# Irrigatron.net
KiCad netlist of a schematic drawn in EasyEDA
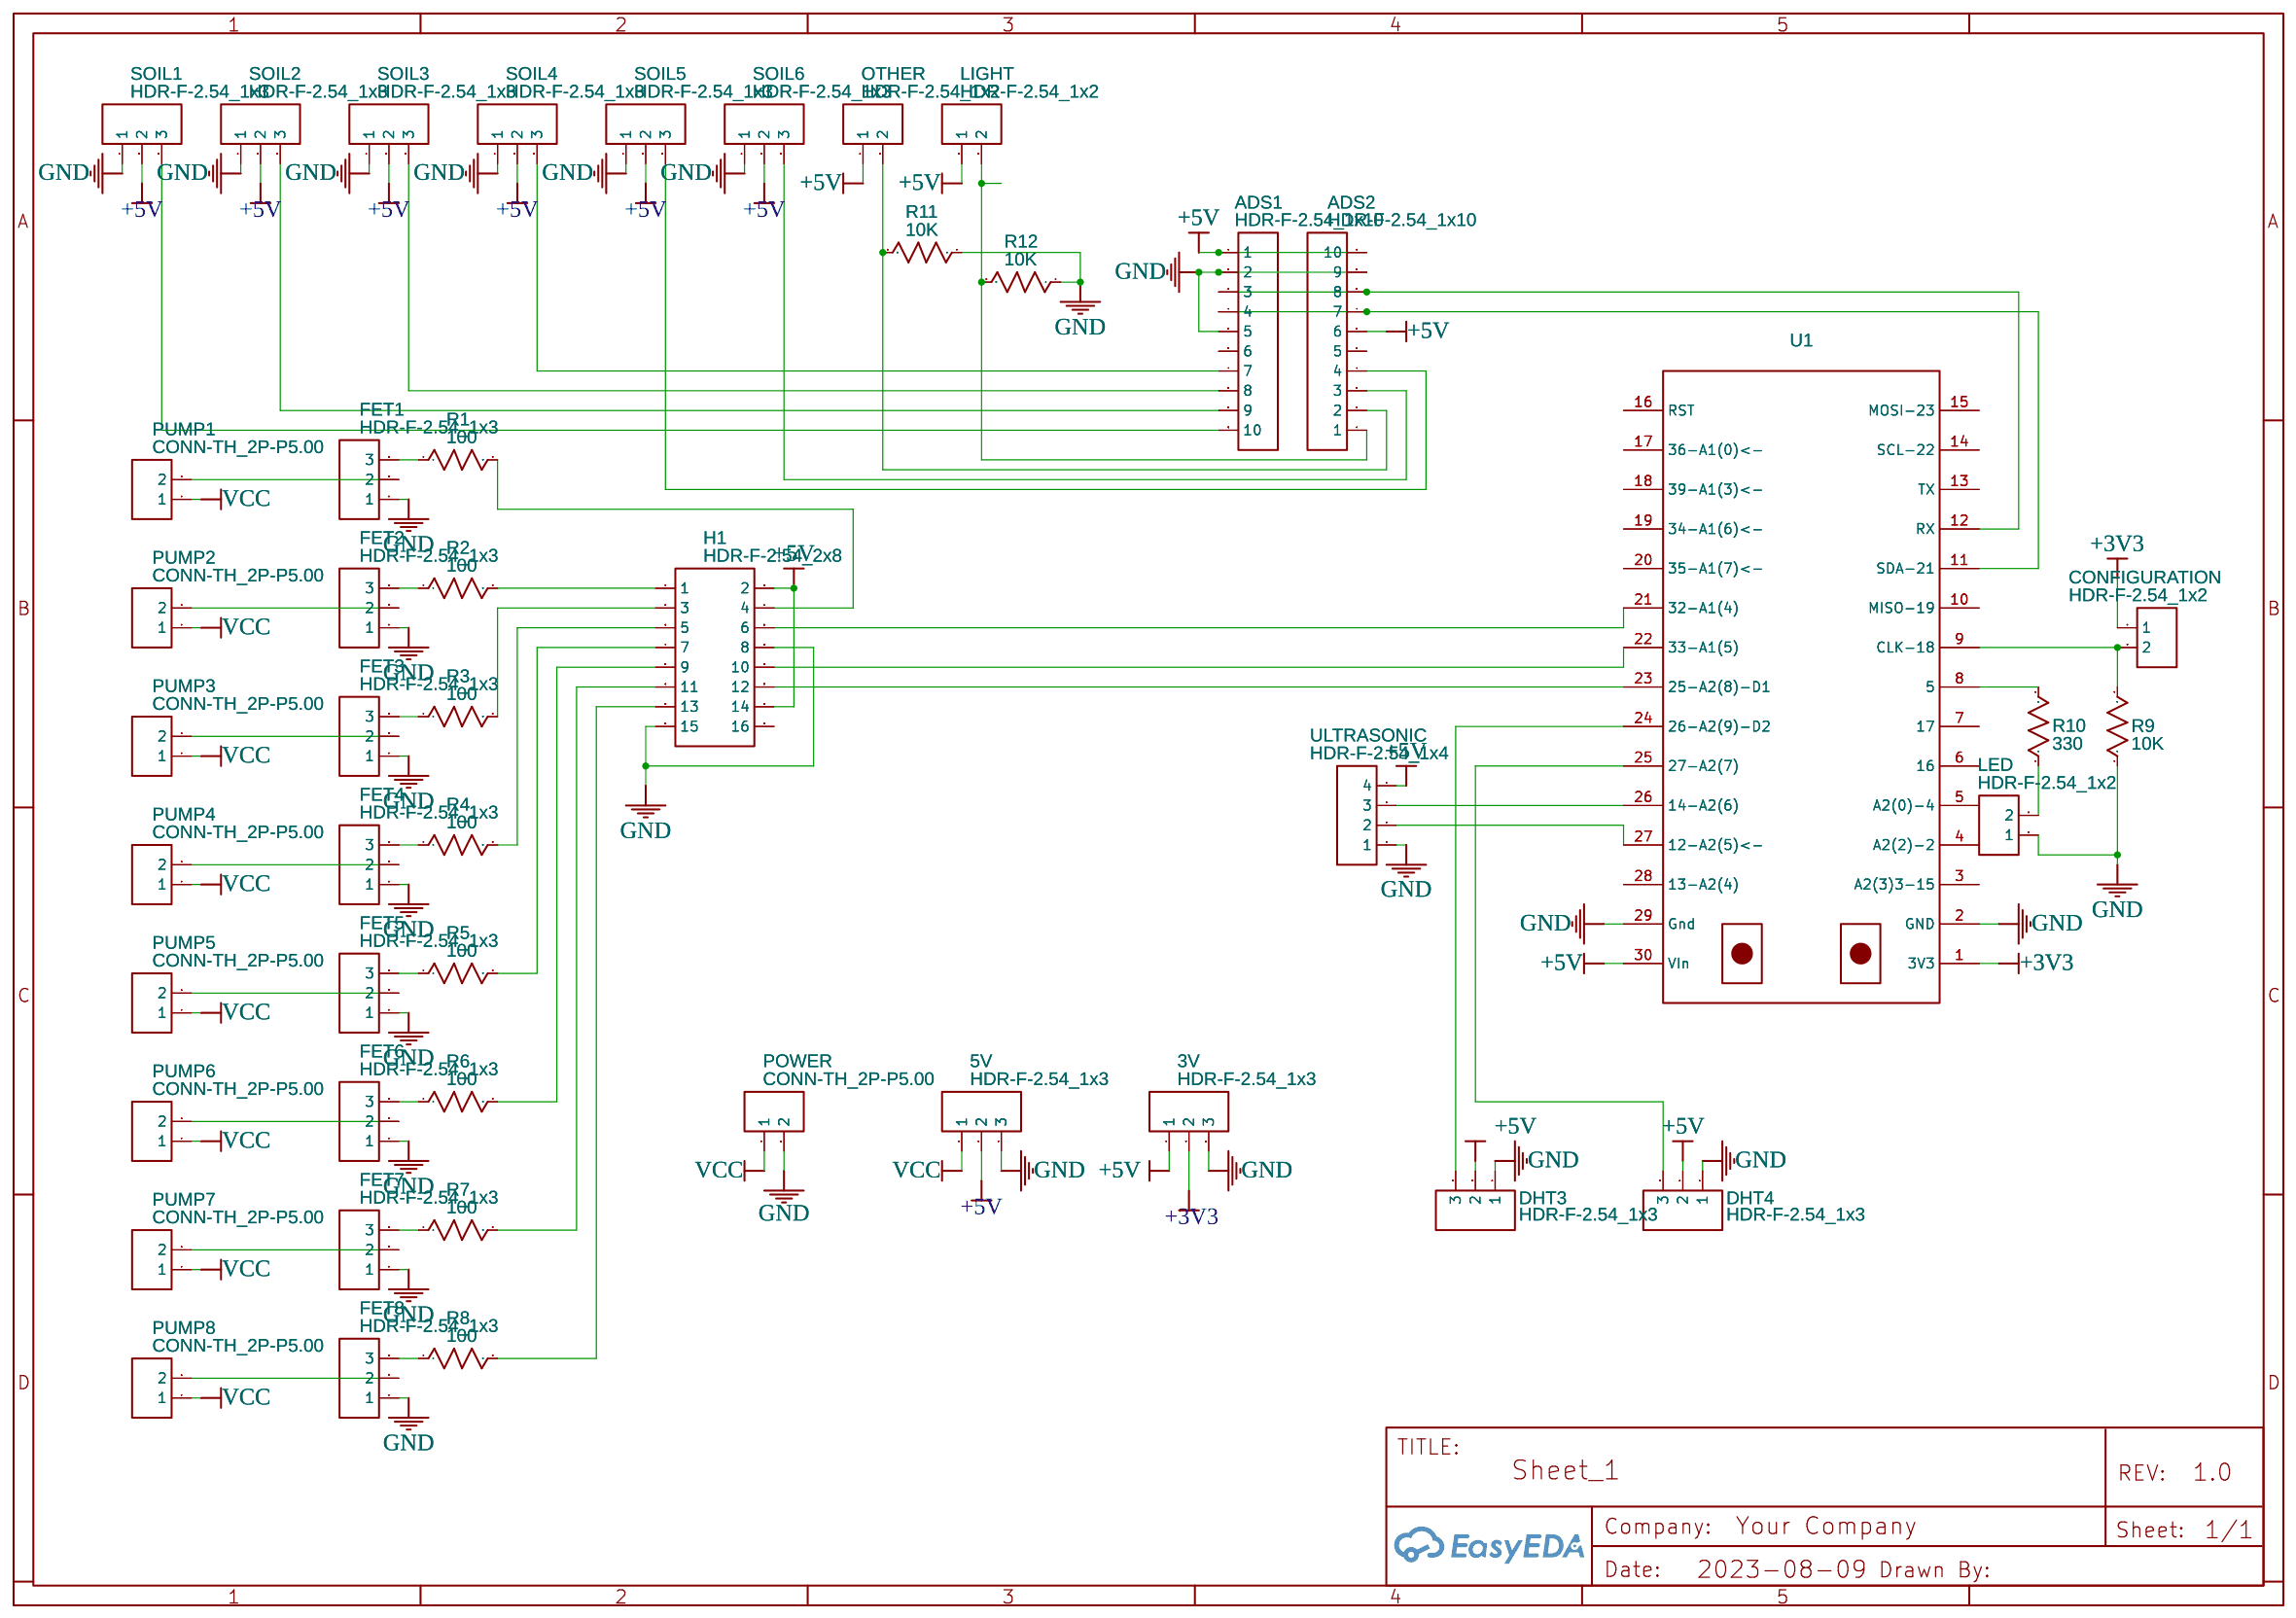
[diagram p0: schematic sheet]

(export (version "E")
  (design (tool "Eeschema 10.0.6"))
  (components
    (comp (ref "3V") (value "HDR-F-2.54_1x3") (libsource (lib "") (part "HDR-F-2.54_1x3_2")))
    (comp (ref "5V") (value "HDR-F-2.54_1x3") (libsource (lib "") (part "HDR-F-2.54_1x3_4")))
    (comp (ref "ADS1") (value "HDR-F-2.54_1x10") (libsource (lib "") (part "HDR-F-2.54_1x10")))
    (comp (ref "ADS2") (value "HDR-F-2.54_1x10") (libsource (lib "") (part "HDR-F-2.54_1x10_1")))
    (comp (ref "CONFIGURATION") (value "HDR-F-2.54_1x2") (libsource (lib "") (part "HDR-F-2.54_1x2_2")))
    (comp (ref "DHT3") (value "HDR-F-2.54_1x3") (libsource (lib "") (part "HDR-F-2.54_1x3_1")))
    (comp (ref "DHT4") (value "HDR-F-2.54_1x3") (libsource (lib "") (part "HDR-F-2.54_1x3_1")))
    (comp (ref "FET1") (value "HDR-F-2.54_1x3") (libsource (lib "") (part "HDR-F-2.54_1x3")))
    (comp (ref "FET2") (value "HDR-F-2.54_1x3") (libsource (lib "") (part "HDR-F-2.54_1x3")))
    (comp (ref "FET3") (value "HDR-F-2.54_1x3") (libsource (lib "") (part "HDR-F-2.54_1x3")))
    (comp (ref "FET4") (value "HDR-F-2.54_1x3") (libsource (lib "") (part "HDR-F-2.54_1x3")))
    (comp (ref "FET5") (value "HDR-F-2.54_1x3") (libsource (lib "") (part "HDR-F-2.54_1x3")))
    (comp (ref "FET6") (value "HDR-F-2.54_1x3") (libsource (lib "") (part "HDR-F-2.54_1x3")))
    (comp (ref "FET7") (value "HDR-F-2.54_1x3") (libsource (lib "") (part "HDR-F-2.54_1x3")))
    (comp (ref "FET8") (value "HDR-F-2.54_1x3") (libsource (lib "") (part "HDR-F-2.54_1x3")))
    (comp (ref "H1") (value "HDR-F-2.54_2x8") (libsource (lib "") (part "HDR-F-2.54_2x8")))
    (comp (ref "LED") (value "HDR-F-2.54_1x2") (libsource (lib "") (part "HDR-F-2.54_1x2_1")))
    (comp (ref "LIGHT") (value "HDR-F-2.54_1x2") (libsource (lib "") (part "HDR-F-2.54_1x2_3")))
    (comp (ref "OTHER") (value "HDR-F-2.54_1x2") (libsource (lib "") (part "HDR-F-2.54_1x2")))
    (comp (ref "POWER") (value "CONN-TH_2P-P5.00") (libsource (lib "") (part "CONN-TH_2P-P5.00_1")))
    (comp (ref "PUMP1") (value "CONN-TH_2P-P5.00") (libsource (lib "") (part "CONN-TH_2P-P5.00")))
    (comp (ref "PUMP2") (value "CONN-TH_2P-P5.00") (libsource (lib "") (part "CONN-TH_2P-P5.00")))
    (comp (ref "PUMP3") (value "CONN-TH_2P-P5.00") (libsource (lib "") (part "CONN-TH_2P-P5.00")))
    (comp (ref "PUMP4") (value "CONN-TH_2P-P5.00") (libsource (lib "") (part "CONN-TH_2P-P5.00")))
    (comp (ref "PUMP5") (value "CONN-TH_2P-P5.00") (libsource (lib "") (part "CONN-TH_2P-P5.00")))
    (comp (ref "PUMP6") (value "CONN-TH_2P-P5.00") (libsource (lib "") (part "CONN-TH_2P-P5.00")))
    (comp (ref "PUMP7") (value "CONN-TH_2P-P5.00") (libsource (lib "") (part "CONN-TH_2P-P5.00")))
    (comp (ref "PUMP8") (value "CONN-TH_2P-P5.00") (libsource (lib "") (part "CONN-TH_2P-P5.00")))
    (comp (ref "R1") (value "100") (libsource (lib "") (part "R_0603_US")))
    (comp (ref "R2") (value "100") (libsource (lib "") (part "R_0603_US")))
    (comp (ref "R3") (value "100") (libsource (lib "") (part "R_0603_US")))
    (comp (ref "R4") (value "100") (libsource (lib "") (part "R_0603_US")))
    (comp (ref "R5") (value "100") (libsource (lib "") (part "R_0603_US")))
    (comp (ref "R6") (value "100") (libsource (lib "") (part "R_0603_US")))
    (comp (ref "R7") (value "100") (libsource (lib "") (part "R_0603_US")))
    (comp (ref "R8") (value "100") (libsource (lib "") (part "R_0603_US")))
    (comp (ref "R9") (value "10K") (libsource (lib "") (part "R_0603_US_2")))
    (comp (ref "R10") (value "330") (libsource (lib "") (part "R_0603_US_2")))
    (comp (ref "R11") (value "10K") (libsource (lib "") (part "R_0603_US_1")))
    (comp (ref "R12") (value "10K") (libsource (lib "") (part "R_0603_US_1")))
    (comp (ref "SOIL1") (value "HDR-F-2.54_1x3") (libsource (lib "") (part "HDR-F-2.54_1x3_3")))
    (comp (ref "SOIL2") (value "HDR-F-2.54_1x3") (libsource (lib "") (part "HDR-F-2.54_1x3_3")))
    (comp (ref "SOIL3") (value "HDR-F-2.54_1x3") (libsource (lib "") (part "HDR-F-2.54_1x3_3")))
    (comp (ref "SOIL4") (value "HDR-F-2.54_1x3") (libsource (lib "") (part "HDR-F-2.54_1x3_3")))
    (comp (ref "SOIL5") (value "HDR-F-2.54_1x3") (libsource (lib "") (part "HDR-F-2.54_1x3_3")))
    (comp (ref "SOIL6") (value "HDR-F-2.54_1x3") (libsource (lib "") (part "HDR-F-2.54_1x3_3")))
    (comp (ref "U1") (value "NO") (libsource (lib "") (part "DOIT ESP32 DEVKIT V1 (30pins)")))
    (comp (ref "ULTRASONIC") (value "HDR-F-2.54_1x4") (libsource (lib "") (part "HDR-F-2.54_1x4")))
  )
  (nets
    (net (code "1") (name "+3V3") (class "Default")
      (node (ref "3V") (pin "2") (pinfunction "2_2") (pintype "input"))
      (node (ref "CONFIGURATION") (pin "1") (pinfunction "1_1") (pintype "input"))
      (node (ref "U1") (pin "1") (pinfunction "3V3_1") (pintype "unspecified"))
    )
    (net (code "2") (name "+5V") (class "Default")
      (node (ref "3V") (pin "1") (pinfunction "1_1") (pintype "input"))
      (node (ref "5V") (pin "2") (pinfunction "2_2") (pintype "input"))
      (node (ref "ADS1") (pin "1") (pinfunction "1_1") (pintype "unspecified"))
      (node (ref "ADS2") (pin "10") (pinfunction "10_10") (pintype "unspecified"))
      (node (ref "ADS2") (pin "6") (pinfunction "6_6") (pintype "unspecified"))
      (node (ref "DHT3") (pin "2") (pinfunction "2_2") (pintype "input"))
      (node (ref "DHT4") (pin "2") (pinfunction "2_2") (pintype "input"))
      (node (ref "H1") (pin "14") (pinfunction "14_14") (pintype "input"))
      (node (ref "H1") (pin "2") (pinfunction "2_2") (pintype "input"))
      (node (ref "LIGHT") (pin "1") (pinfunction "1_1") (pintype "input"))
      (node (ref "OTHER") (pin "1") (pinfunction "1_1") (pintype "input"))
      (node (ref "SOIL1") (pin "2") (pinfunction "2_2") (pintype "input"))
      (node (ref "SOIL2") (pin "2") (pinfunction "2_2") (pintype "input"))
      (node (ref "SOIL3") (pin "2") (pinfunction "2_2") (pintype "input"))
      (node (ref "SOIL4") (pin "2") (pinfunction "2_2") (pintype "input"))
      (node (ref "SOIL5") (pin "2") (pinfunction "2_2") (pintype "input"))
      (node (ref "SOIL6") (pin "2") (pinfunction "2_2") (pintype "input"))
      (node (ref "U1") (pin "30") (pinfunction "VIn_30") (pintype "unspecified"))
      (node (ref "ULTRASONIC") (pin "4") (pinfunction "4_4") (pintype "unspecified"))
    )
    (net (code "3") (name "GND") (class "Default")
      (node (ref "3V") (pin "3") (pinfunction "3_3") (pintype "input"))
      (node (ref "5V") (pin "3") (pinfunction "3_3") (pintype "input"))
      (node (ref "ADS1") (pin "2") (pinfunction "2_2") (pintype "unspecified"))
      (node (ref "ADS1") (pin "5") (pinfunction "5_5") (pintype "unspecified"))
      (node (ref "ADS2") (pin "9") (pinfunction "9_9") (pintype "unspecified"))
      (node (ref "DHT3") (pin "1") (pinfunction "1_1") (pintype "input"))
      (node (ref "DHT4") (pin "1") (pinfunction "1_1") (pintype "input"))
      (node (ref "FET1") (pin "1") (pinfunction "1_1") (pintype "input"))
      (node (ref "FET2") (pin "1") (pinfunction "1_1") (pintype "input"))
      (node (ref "FET3") (pin "1") (pinfunction "1_1") (pintype "input"))
      (node (ref "FET4") (pin "1") (pinfunction "1_1") (pintype "input"))
      (node (ref "FET5") (pin "1") (pinfunction "1_1") (pintype "input"))
      (node (ref "FET6") (pin "1") (pinfunction "1_1") (pintype "input"))
      (node (ref "FET7") (pin "1") (pinfunction "1_1") (pintype "input"))
      (node (ref "FET8") (pin "1") (pinfunction "1_1") (pintype "input"))
      (node (ref "H1") (pin "15") (pinfunction "15_15") (pintype "input"))
      (node (ref "H1") (pin "8") (pinfunction "8_8") (pintype "input"))
      (node (ref "LED") (pin "1") (pinfunction "1_1") (pintype "input"))
      (node (ref "POWER") (pin "2") (pinfunction "2_2") (pintype "unspecified"))
      (node (ref "R11") (pin "1") (pinfunction "1_1") (pintype "unspecified"))
      (node (ref "R12") (pin "1") (pinfunction "1_1") (pintype "unspecified"))
      (node (ref "R9") (pin "1") (pinfunction "1_1") (pintype "unspecified"))
      (node (ref "SOIL1") (pin "1") (pinfunction "1_1") (pintype "input"))
      (node (ref "SOIL2") (pin "1") (pinfunction "1_1") (pintype "input"))
      (node (ref "SOIL3") (pin "1") (pinfunction "1_1") (pintype "input"))
      (node (ref "SOIL4") (pin "1") (pinfunction "1_1") (pintype "input"))
      (node (ref "SOIL5") (pin "1") (pinfunction "1_1") (pintype "input"))
      (node (ref "SOIL6") (pin "1") (pinfunction "1_1") (pintype "input"))
      (node (ref "U1") (pin "2") (pinfunction "GND_2") (pintype "unspecified"))
      (node (ref "U1") (pin "29") (pinfunction "Gnd_29") (pintype "unspecified"))
      (node (ref "ULTRASONIC") (pin "1") (pinfunction "1_1") (pintype "unspecified"))
    )
    (net (code "4") (name "Net-(ADS1-Pad7)") (class "Default")
      (node (ref "ADS1") (pin "7") (pinfunction "7_7") (pintype "unspecified"))
      (node (ref "SOIL4") (pin "3") (pinfunction "3_3") (pintype "input"))
    )
    (net (code "5") (name "Net-(ADS1-Pad8)") (class "Default")
      (node (ref "ADS1") (pin "8") (pinfunction "8_8") (pintype "unspecified"))
      (node (ref "SOIL3") (pin "3") (pinfunction "3_3") (pintype "input"))
    )
    (net (code "6") (name "Net-(ADS1-Pad9)") (class "Default")
      (node (ref "ADS1") (pin "9") (pinfunction "9_9") (pintype "unspecified"))
      (node (ref "SOIL2") (pin "3") (pinfunction "3_3") (pintype "input"))
    )
    (net (code "7") (name "Net-(ADS1-Pad10)") (class "Default")
      (node (ref "ADS1") (pin "10") (pinfunction "10_10") (pintype "unspecified"))
      (node (ref "SOIL1") (pin "3") (pinfunction "3_3") (pintype "input"))
    )
    (net (code "8") (name "Net-(ADS2-Pad1)") (class "Default")
      (node (ref "ADS2") (pin "1") (pinfunction "1_1") (pintype "unspecified"))
      (node (ref "LIGHT") (pin "2") (pinfunction "2_2") (pintype "input"))
      (node (ref "R12") (pin "2") (pinfunction "2_2") (pintype "unspecified"))
    )
    (net (code "9") (name "Net-(ADS2-Pad2)") (class "Default")
      (node (ref "ADS2") (pin "2") (pinfunction "2_2") (pintype "unspecified"))
      (node (ref "OTHER") (pin "2") (pinfunction "2_2") (pintype "input"))
      (node (ref "R11") (pin "2") (pinfunction "2_2") (pintype "unspecified"))
    )
    (net (code "10") (name "Net-(ADS2-Pad3)") (class "Default")
      (node (ref "ADS2") (pin "3") (pinfunction "3_3") (pintype "unspecified"))
      (node (ref "SOIL6") (pin "3") (pinfunction "3_3") (pintype "input"))
    )
    (net (code "11") (name "Net-(ADS2-Pad4)") (class "Default")
      (node (ref "ADS2") (pin "4") (pinfunction "4_4") (pintype "unspecified"))
      (node (ref "SOIL5") (pin "3") (pinfunction "3_3") (pintype "input"))
    )
    (net (code "12") (name "Net-(FET1-Pad2)") (class "Default")
      (node (ref "FET1") (pin "2") (pinfunction "2_2") (pintype "input"))
      (node (ref "PUMP1") (pin "2") (pinfunction "2_2") (pintype "unspecified"))
    )
    (net (code "13") (name "Net-(FET1-Pad3)") (class "Default")
      (node (ref "FET1") (pin "3") (pinfunction "3_3") (pintype "input"))
      (node (ref "R1") (pin "1") (pinfunction "1_1") (pintype "unspecified"))
    )
    (net (code "14") (name "Net-(FET2-Pad2)") (class "Default")
      (node (ref "FET2") (pin "2") (pinfunction "2_2") (pintype "input"))
      (node (ref "PUMP2") (pin "2") (pinfunction "2_2") (pintype "unspecified"))
    )
    (net (code "15") (name "Net-(FET2-Pad3)") (class "Default")
      (node (ref "FET2") (pin "3") (pinfunction "3_3") (pintype "input"))
      (node (ref "R2") (pin "1") (pinfunction "1_1") (pintype "unspecified"))
    )
    (net (code "16") (name "Net-(FET3-Pad2)") (class "Default")
      (node (ref "FET3") (pin "2") (pinfunction "2_2") (pintype "input"))
      (node (ref "PUMP3") (pin "2") (pinfunction "2_2") (pintype "unspecified"))
    )
    (net (code "17") (name "Net-(FET3-Pad3)") (class "Default")
      (node (ref "FET3") (pin "3") (pinfunction "3_3") (pintype "input"))
      (node (ref "R3") (pin "1") (pinfunction "1_1") (pintype "unspecified"))
    )
    (net (code "18") (name "Net-(FET4-Pad2)") (class "Default")
      (node (ref "FET4") (pin "2") (pinfunction "2_2") (pintype "input"))
      (node (ref "PUMP4") (pin "2") (pinfunction "2_2") (pintype "unspecified"))
    )
    (net (code "19") (name "Net-(FET4-Pad3)") (class "Default")
      (node (ref "FET4") (pin "3") (pinfunction "3_3") (pintype "input"))
      (node (ref "R4") (pin "1") (pinfunction "1_1") (pintype "unspecified"))
    )
    (net (code "20") (name "Net-(FET5-Pad2)") (class "Default")
      (node (ref "FET5") (pin "2") (pinfunction "2_2") (pintype "input"))
      (node (ref "PUMP5") (pin "2") (pinfunction "2_2") (pintype "unspecified"))
    )
    (net (code "21") (name "Net-(FET5-Pad3)") (class "Default")
      (node (ref "FET5") (pin "3") (pinfunction "3_3") (pintype "input"))
      (node (ref "R5") (pin "1") (pinfunction "1_1") (pintype "unspecified"))
    )
    (net (code "22") (name "Net-(FET6-Pad2)") (class "Default")
      (node (ref "FET6") (pin "2") (pinfunction "2_2") (pintype "input"))
      (node (ref "PUMP6") (pin "2") (pinfunction "2_2") (pintype "unspecified"))
    )
    (net (code "23") (name "Net-(FET6-Pad3)") (class "Default")
      (node (ref "FET6") (pin "3") (pinfunction "3_3") (pintype "input"))
      (node (ref "R6") (pin "1") (pinfunction "1_1") (pintype "unspecified"))
    )
    (net (code "24") (name "Net-(FET7-Pad2)") (class "Default")
      (node (ref "FET7") (pin "2") (pinfunction "2_2") (pintype "input"))
      (node (ref "PUMP7") (pin "2") (pinfunction "2_2") (pintype "unspecified"))
    )
    (net (code "25") (name "Net-(FET7-Pad3)") (class "Default")
      (node (ref "FET7") (pin "3") (pinfunction "3_3") (pintype "input"))
      (node (ref "R7") (pin "1") (pinfunction "1_1") (pintype "unspecified"))
    )
    (net (code "26") (name "Net-(FET8-Pad2)") (class "Default")
      (node (ref "FET8") (pin "2") (pinfunction "2_2") (pintype "input"))
      (node (ref "PUMP8") (pin "2") (pinfunction "2_2") (pintype "unspecified"))
    )
    (net (code "27") (name "Net-(FET8-Pad3)") (class "Default")
      (node (ref "FET8") (pin "3") (pinfunction "3_3") (pintype "input"))
      (node (ref "R8") (pin "1") (pinfunction "1_1") (pintype "unspecified"))
    )
    (net (code "28") (name "Net-(H1-Pad1)") (class "Default")
      (node (ref "H1") (pin "1") (pinfunction "1_1") (pintype "input"))
      (node (ref "R2") (pin "2") (pinfunction "2_2") (pintype "unspecified"))
    )
    (net (code "29") (name "Net-(H1-Pad3)") (class "Default")
      (node (ref "H1") (pin "3") (pinfunction "3_3") (pintype "input"))
      (node (ref "R3") (pin "2") (pinfunction "2_2") (pintype "unspecified"))
    )
    (net (code "30") (name "Net-(H1-Pad4)") (class "Default")
      (node (ref "H1") (pin "4") (pinfunction "4_4") (pintype "input"))
      (node (ref "R1") (pin "2") (pinfunction "2_2") (pintype "unspecified"))
    )
    (net (code "31") (name "Net-(H1-Pad5)") (class "Default")
      (node (ref "H1") (pin "5") (pinfunction "5_5") (pintype "input"))
      (node (ref "R4") (pin "2") (pinfunction "2_2") (pintype "unspecified"))
    )
    (net (code "32") (name "Net-(H1-Pad7)") (class "Default")
      (node (ref "H1") (pin "7") (pinfunction "7_7") (pintype "input"))
      (node (ref "R5") (pin "2") (pinfunction "2_2") (pintype "unspecified"))
    )
    (net (code "33") (name "Net-(H1-Pad9)") (class "Default")
      (node (ref "H1") (pin "9") (pinfunction "9_9") (pintype "input"))
      (node (ref "R6") (pin "2") (pinfunction "2_2") (pintype "unspecified"))
    )
    (net (code "34") (name "Net-(H1-Pad11)") (class "Default")
      (node (ref "H1") (pin "11") (pinfunction "11_11") (pintype "input"))
      (node (ref "R7") (pin "2") (pinfunction "2_2") (pintype "unspecified"))
    )
    (net (code "35") (name "Net-(H1-Pad13)") (class "Default")
      (node (ref "H1") (pin "13") (pinfunction "13_13") (pintype "input"))
      (node (ref "R8") (pin "2") (pinfunction "2_2") (pintype "unspecified"))
    )
    (net (code "36") (name "Net-(LED-Pad2)") (class "Default")
      (node (ref "LED") (pin "2") (pinfunction "2_2") (pintype "input"))
      (node (ref "R10") (pin "1") (pinfunction "1_1") (pintype "unspecified"))
    )
    (net (code "37") (name "Net-(U1-5)") (class "Default")
      (node (ref "R10") (pin "2") (pinfunction "2_2") (pintype "unspecified"))
      (node (ref "U1") (pin "8") (pinfunction "5_8") (pintype "unspecified"))
    )
    (net (code "38") (name "Net-(U1-12-A2(5)<-)") (class "Default")
      (node (ref "U1") (pin "27") (pinfunction "12-A2(5)<-_27") (pintype "unspecified"))
      (node (ref "ULTRASONIC") (pin "2") (pinfunction "2_2") (pintype "unspecified"))
    )
    (net (code "39") (name "Net-(U1-14-A2(6))") (class "Default")
      (node (ref "U1") (pin "26") (pinfunction "14-A2(6)_26") (pintype "unspecified"))
      (node (ref "ULTRASONIC") (pin "3") (pinfunction "3_3") (pintype "unspecified"))
    )
    (net (code "40") (name "Net-(U1-25-A2(8)-D1)") (class "Default")
      (node (ref "H1") (pin "12") (pinfunction "12_12") (pintype "input"))
      (node (ref "U1") (pin "23") (pinfunction "25-A2(8)-D1_23") (pintype "unspecified"))
    )
    (net (code "41") (name "Net-(U1-26-A2(9)-D2)") (class "Default")
      (node (ref "DHT3") (pin "3") (pinfunction "3_3") (pintype "input"))
      (node (ref "U1") (pin "24") (pinfunction "26-A2(9)-D2_24") (pintype "unspecified"))
    )
    (net (code "42") (name "Net-(U1-27-A2(7))") (class "Default")
      (node (ref "DHT4") (pin "3") (pinfunction "3_3") (pintype "input"))
      (node (ref "U1") (pin "25") (pinfunction "27-A2(7)_25") (pintype "unspecified"))
    )
    (net (code "43") (name "Net-(U1-32-A1(4))") (class "Default")
      (node (ref "H1") (pin "6") (pinfunction "6_6") (pintype "input"))
      (node (ref "U1") (pin "21") (pinfunction "32-A1(4)_21") (pintype "unspecified"))
    )
    (net (code "44") (name "Net-(U1-33-A1(5))") (class "Default")
      (node (ref "H1") (pin "10") (pinfunction "10_10") (pintype "input"))
      (node (ref "U1") (pin "22") (pinfunction "33-A1(5)_22") (pintype "unspecified"))
    )
    (net (code "45") (name "Net-(U1-CLK-18)") (class "Default")
      (node (ref "CONFIGURATION") (pin "2") (pinfunction "2_2") (pintype "input"))
      (node (ref "R9") (pin "2") (pinfunction "2_2") (pintype "unspecified"))
      (node (ref "U1") (pin "9") (pinfunction "CLK-18_9") (pintype "unspecified"))
    )
    (net (code "46") (name "Net-(U1-RX)") (class "Default")
      (node (ref "ADS1") (pin "3") (pinfunction "3_3") (pintype "unspecified"))
      (node (ref "ADS2") (pin "8") (pinfunction "8_8") (pintype "unspecified"))
      (node (ref "U1") (pin "12") (pinfunction "RX_12") (pintype "unspecified"))
    )
    (net (code "47") (name "Net-(U1-SDA-21)") (class "Default")
      (node (ref "ADS1") (pin "4") (pinfunction "4_4") (pintype "unspecified"))
      (node (ref "ADS2") (pin "7") (pinfunction "7_7") (pintype "unspecified"))
      (node (ref "U1") (pin "11") (pinfunction "SDA-21_11") (pintype "unspecified"))
    )
    (net (code "48") (name "VCC") (class "Default")
      (node (ref "5V") (pin "1") (pinfunction "1_1") (pintype "input"))
      (node (ref "POWER") (pin "1") (pinfunction "1_1") (pintype "unspecified"))
      (node (ref "PUMP1") (pin "1") (pinfunction "1_1") (pintype "unspecified"))
      (node (ref "PUMP2") (pin "1") (pinfunction "1_1") (pintype "unspecified"))
      (node (ref "PUMP3") (pin "1") (pinfunction "1_1") (pintype "unspecified"))
      (node (ref "PUMP4") (pin "1") (pinfunction "1_1") (pintype "unspecified"))
      (node (ref "PUMP5") (pin "1") (pinfunction "1_1") (pintype "unspecified"))
      (node (ref "PUMP6") (pin "1") (pinfunction "1_1") (pintype "unspecified"))
      (node (ref "PUMP7") (pin "1") (pinfunction "1_1") (pintype "unspecified"))
      (node (ref "PUMP8") (pin "1") (pinfunction "1_1") (pintype "unspecified"))
    )
    (net (code "49") (name "unconnected-(ADS1-Pad6)") (class "Default")
      (node (ref "ADS1") (pin "6") (pinfunction "6_6") (pintype "unspecified"))
    )
    (net (code "50") (name "unconnected-(ADS2-Pad5)") (class "Default")
      (node (ref "ADS2") (pin "5") (pinfunction "5_5") (pintype "unspecified"))
    )
    (net (code "51") (name "unconnected-(H1-Pad16)") (class "Default")
      (node (ref "H1") (pin "16") (pinfunction "16_16") (pintype "input"))
    )
    (net (code "52") (name "unconnected-(U1-13-A2(4)-Pad28)") (class "Default")
      (node (ref "U1") (pin "28") (pinfunction "13-A2(4)_28") (pintype "unspecified"))
    )
    (net (code "53") (name "unconnected-(U1-16-Pad6)") (class "Default")
      (node (ref "U1") (pin "6") (pinfunction "16_6") (pintype "unspecified"))
    )
    (net (code "54") (name "unconnected-(U1-17-Pad7)") (class "Default")
      (node (ref "U1") (pin "7") (pinfunction "17_7") (pintype "unspecified"))
    )
    (net (code "55") (name "unconnected-(U1-34-A1(6)<--Pad19)") (class "Default")
      (node (ref "U1") (pin "19") (pinfunction "34-A1(6)<-_19") (pintype "unspecified"))
    )
    (net (code "56") (name "unconnected-(U1-35-A1(7)<--Pad20)") (class "Default")
      (node (ref "U1") (pin "20") (pinfunction "35-A1(7)<-_20") (pintype "unspecified"))
    )
    (net (code "57") (name "unconnected-(U1-36-A1(0)<--Pad17)") (class "Default")
      (node (ref "U1") (pin "17") (pinfunction "36-A1(0)<-_17") (pintype "unspecified"))
    )
    (net (code "58") (name "unconnected-(U1-39-A1(3)<--Pad18)") (class "Default")
      (node (ref "U1") (pin "18") (pinfunction "39-A1(3)<-_18") (pintype "unspecified"))
    )
    (net (code "59") (name "unconnected-(U1-A2(0)-4-Pad5)") (class "Default")
      (node (ref "U1") (pin "5") (pinfunction "A2(0)-4_5") (pintype "unspecified"))
    )
    (net (code "60") (name "unconnected-(U1-A2(2)-2-Pad4)") (class "Default")
      (node (ref "U1") (pin "4") (pinfunction "A2(2)-2_4") (pintype "unspecified"))
    )
    (net (code "61") (name "unconnected-(U1-A2(3)3-15-Pad3)") (class "Default")
      (node (ref "U1") (pin "3") (pinfunction "A2(3)3-15_3") (pintype "unspecified"))
    )
    (net (code "62") (name "unconnected-(U1-MISO-19-Pad10)") (class "Default")
      (node (ref "U1") (pin "10") (pinfunction "MISO-19_10") (pintype "unspecified"))
    )
    (net (code "63") (name "unconnected-(U1-MOSI-23-Pad15)") (class "Default")
      (node (ref "U1") (pin "15") (pinfunction "MOSI-23_15") (pintype "unspecified"))
    )
    (net (code "64") (name "unconnected-(U1-RST-Pad16)") (class "Default")
      (node (ref "U1") (pin "16") (pinfunction "RST_16") (pintype "unspecified"))
    )
    (net (code "65") (name "unconnected-(U1-SCL-22-Pad14)") (class "Default")
      (node (ref "U1") (pin "14") (pinfunction "SCL-22_14") (pintype "unspecified"))
    )
    (net (code "66") (name "unconnected-(U1-TX-Pad13)") (class "Default")
      (node (ref "U1") (pin "13") (pinfunction "TX_13") (pintype "unspecified"))
    )
  )
)
